# testsmd.net
KiCad netlist of a schematic drawn in EAGLE
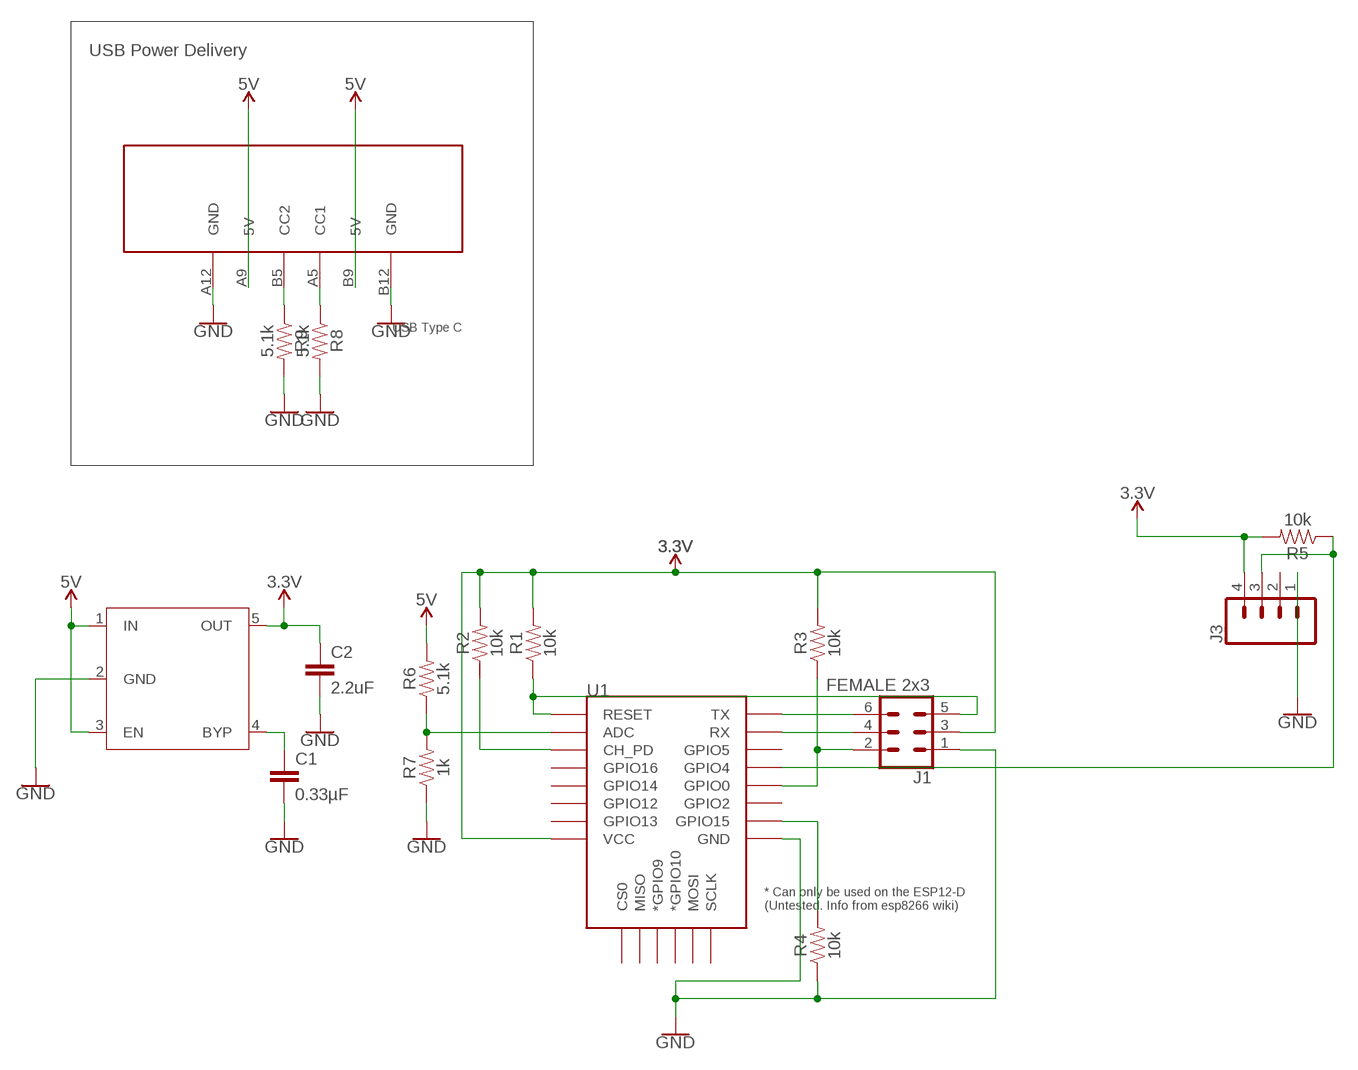
[diagram p0: schematic, sheet 1]

(export (version "E")
  (design (tool "Eeschema 10.0.6"))
  (components
    (comp (ref "C1")
      (value "0.33µF")
      (footprint "eagle-import:0805")
      (libsource (lib "eagle-import") (part "0.33UF/330NF-0805-50V-10%"))
    )
    (comp (ref "C2")
      (value "2.2uF")
      (footprint "eagle-import:1206")
      (libsource (lib "eagle-import") (part "2.2UF-1206-50V-10%"))
    )
    (comp (ref "J1")
      (value "FEMALE 2x3")
      (footprint "eagle-import:2X3")
      (libsource (lib "eagle-import") (part "CONN_03X2FEMALE"))
    )
    (comp (ref "J3")
      (value "CONN_04")
      (footprint "eagle-import:1X04")
      (libsource (lib "eagle-import") (part "CONN_04"))
    )
    (comp (ref "R1")
      (value "10k")
      (footprint "eagle-import:0805")
      (libsource (lib "eagle-import") (part "0.75OHM-0805-1/4W-1%"))
    )
    (comp (ref "R2")
      (value "10k")
      (footprint "eagle-import:0805")
      (libsource (lib "eagle-import") (part "0.75OHM-0805-1/4W-1%"))
    )
    (comp (ref "R3")
      (value "10k")
      (footprint "eagle-import:0805")
      (libsource (lib "eagle-import") (part "0.75OHM-0805-1/4W-1%"))
    )
    (comp (ref "R4")
      (value "10k")
      (footprint "eagle-import:0805")
      (libsource (lib "eagle-import") (part "0.75OHM-0805-1/4W-1%"))
    )
    (comp (ref "R5")
      (value "10k")
      (footprint "eagle-import:0805")
      (libsource (lib "eagle-import") (part "0.75OHM-0805-1/4W-1%"))
    )
    (comp (ref "R6")
      (value "5.1k")
      (footprint "eagle-import:0805")
      (libsource (lib "eagle-import") (part "0.75OHM-0805-1/4W-1%"))
    )
    (comp (ref "R7")
      (value "1k")
      (footprint "eagle-import:0805")
      (libsource (lib "eagle-import") (part "0.75OHM-0805-1/4W-1%"))
    )
    (comp (ref "R8")
      (value "5.1k")
      (footprint "eagle-import:0805")
      (libsource (lib "eagle-import") (part "0.75OHM-0805-1/4W-1%"))
    )
    (comp (ref "R9")
      (value "5.1k")
      (footprint "eagle-import:0805")
      (libsource (lib "eagle-import") (part "0.75OHM-0805-1/4W-1%"))
    )
    (comp (ref "U$1")
      (value "MIC5219")
      (footprint "eagle-import:SOT95P280X145-5N")
      (libsource (lib "eagle-import") (part "MIC5219"))
    )
    (comp (ref "U$3")
      (value "USBC6PIN")
      (footprint "eagle-import:USBC6PIN")
      (libsource (lib "eagle-import") (part "USBC6PIN"))
    )
    (comp (ref "U1")
      (value "ESP12ESMD")
      (footprint "eagle-import:ESP12E-SMD")
      (libsource (lib "eagle-import") (part "ESP12ESMD"))
    )
  )
  (nets
    (net (code "1") (name "3.3V") (class "Default")
      (node (ref "C2") (pin "1") (pinfunction "1_1") (pintype "passive"))
      (node (ref "J1") (pin "3") (pinfunction "3_3") (pintype "bidirectional"))
      (node (ref "J3") (pin "4") (pinfunction "4_4") (pintype "passive"))
      (node (ref "R1") (pin "2") (pinfunction "2_2") (pintype "passive"))
      (node (ref "R2") (pin "2") (pinfunction "2_2") (pintype "passive"))
      (node (ref "R3") (pin "2") (pinfunction "2_2") (pintype "passive"))
      (node (ref "R5") (pin "2") (pinfunction "2_2") (pintype "passive"))
      (node (ref "U$1") (pin "5") (pinfunction "OUT_5") (pintype "bidirectional"))
      (node (ref "U1") (pin "VCC") (pinfunction "VCC_VCC") (pintype "bidirectional"))
    )
    (net (code "2") (name "5V") (class "Default")
      (node (ref "R6") (pin "2") (pinfunction "2_2") (pintype "passive"))
      (node (ref "U$1") (pin "1") (pinfunction "IN_1") (pintype "bidirectional"))
      (node (ref "U$1") (pin "3") (pinfunction "EN_3") (pintype "bidirectional"))
      (node (ref "U$3") (pin "A9") (pinfunction "5V_A9") (pintype "bidirectional"))
      (node (ref "U$3") (pin "B9") (pinfunction "5V_B9") (pintype "bidirectional"))
    )
    (net (code "3") (name "GND") (class "Default")
      (node (ref "C1") (pin "2") (pinfunction "2_2") (pintype "passive"))
      (node (ref "C2") (pin "2") (pinfunction "2_2") (pintype "passive"))
      (node (ref "J1") (pin "1") (pinfunction "1_1") (pintype "bidirectional"))
      (node (ref "J3") (pin "1") (pinfunction "1_1") (pintype "passive"))
      (node (ref "R4") (pin "1") (pinfunction "1_1") (pintype "passive"))
      (node (ref "R7") (pin "1") (pinfunction "1_1") (pintype "passive"))
      (node (ref "R8") (pin "2") (pinfunction "2_2") (pintype "passive"))
      (node (ref "R9") (pin "2") (pinfunction "2_2") (pintype "passive"))
      (node (ref "U$1") (pin "2") (pinfunction "GND_2") (pintype "bidirectional"))
      (node (ref "U$3") (pin "A12") (pinfunction "GND_A12") (pintype "bidirectional"))
      (node (ref "U$3") (pin "B12") (pinfunction "GND_B12") (pintype "bidirectional"))
      (node (ref "U1") (pin "GND") (pinfunction "GND_GND") (pintype "bidirectional"))
    )
    (net (code "4") (name "Net-(J1-Pad2)") (class "Default")
      (node (ref "J1") (pin "2") (pinfunction "2_2") (pintype "bidirectional"))
      (node (ref "R3") (pin "1") (pinfunction "1_1") (pintype "passive"))
      (node (ref "U1") (pin "GPIO0") (pinfunction "GPIO0_GPIO0") (pintype "bidirectional"))
    )
    (net (code "5") (name "Net-(J1-Pad5)") (class "Default")
      (node (ref "J1") (pin "5") (pinfunction "5_5") (pintype "bidirectional"))
      (node (ref "R1") (pin "1") (pinfunction "1_1") (pintype "passive"))
      (node (ref "U1") (pin "RESET") (pinfunction "RESET_RESET") (pintype "bidirectional"))
    )
    (net (code "6") (name "Net-(J3-Pad3)") (class "Default")
      (node (ref "J3") (pin "3") (pinfunction "3_3") (pintype "passive"))
      (node (ref "R5") (pin "1") (pinfunction "1_1") (pintype "passive"))
      (node (ref "U1") (pin "GPIO4") (pinfunction "GPIO4_GPIO4") (pintype "bidirectional"))
    )
    (net (code "7") (name "Net-(R2-Pad1)") (class "Default")
      (node (ref "R2") (pin "1") (pinfunction "1_1") (pintype "passive"))
      (node (ref "U1") (pin "CH_PD") (pinfunction "CH_PD_CH_PD") (pintype "bidirectional"))
    )
    (net (code "8") (name "Net-(R4-Pad2)") (class "Default")
      (node (ref "R4") (pin "2") (pinfunction "2_2") (pintype "passive"))
      (node (ref "U1") (pin "GPIO15") (pinfunction "GPIO15_GPIO15") (pintype "bidirectional"))
    )
    (net (code "9") (name "Net-(R6-Pad1)") (class "Default")
      (node (ref "R6") (pin "1") (pinfunction "1_1") (pintype "passive"))
      (node (ref "R7") (pin "2") (pinfunction "2_2") (pintype "passive"))
      (node (ref "U1") (pin "ADC") (pinfunction "ADC_ADC") (pintype "bidirectional"))
    )
    (net (code "10") (name "Net-(U$1-BYP)") (class "Default")
      (node (ref "C1") (pin "1") (pinfunction "1_1") (pintype "passive"))
      (node (ref "U$1") (pin "4") (pinfunction "BYP_4") (pintype "bidirectional"))
    )
    (net (code "11") (name "Net-(U$3-CC1)") (class "Default")
      (node (ref "R8") (pin "1") (pinfunction "1_1") (pintype "passive"))
      (node (ref "U$3") (pin "A5") (pinfunction "CC1_A5") (pintype "bidirectional"))
    )
    (net (code "12") (name "Net-(U$3-CC2)") (class "Default")
      (node (ref "R9") (pin "1") (pinfunction "1_1") (pintype "passive"))
      (node (ref "U$3") (pin "B5") (pinfunction "CC2_B5") (pintype "bidirectional"))
    )
    (net (code "13") (name "Net-(U1-RX)") (class "Default")
      (node (ref "J1") (pin "4") (pinfunction "4_4") (pintype "bidirectional"))
      (node (ref "U1") (pin "RXD0") (pinfunction "RX_RXD0") (pintype "bidirectional"))
    )
    (net (code "14") (name "Net-(U1-TX)") (class "Default")
      (node (ref "J1") (pin "6") (pinfunction "6_6") (pintype "bidirectional"))
      (node (ref "U1") (pin "TXD0") (pinfunction "TX_TXD0") (pintype "bidirectional"))
    )
    (net (code "15") (name "unconnected-(J3-Pad2)") (class "Default")
      (node (ref "J3") (pin "2") (pinfunction "2_2") (pintype "passive"))
    )
    (net (code "16") (name "unconnected-(U1-*GPIO9-PadGPIO9)") (class "Default")
      (node (ref "U1") (pin "GPIO9") (pinfunction "*GPIO9_GPIO9") (pintype "bidirectional"))
    )
    (net (code "17") (name "unconnected-(U1-*GPIO10-PadGPIO10)") (class "Default")
      (node (ref "U1") (pin "GPIO10") (pinfunction "*GPIO10_GPIO10") (pintype "bidirectional"))
    )
    (net (code "18") (name "unconnected-(U1-PadCS0)") (class "Default")
      (node (ref "U1") (pin "CS0") (pinfunction "CS0_CS0") (pintype "bidirectional"))
    )
    (net (code "19") (name "unconnected-(U1-PadGPIO2)") (class "Default")
      (node (ref "U1") (pin "GPIO2") (pinfunction "GPIO2_GPIO2") (pintype "bidirectional"))
    )
    (net (code "20") (name "unconnected-(U1-PadGPIO5)") (class "Default")
      (node (ref "U1") (pin "GPIO5") (pinfunction "GPIO5_GPIO5") (pintype "bidirectional"))
    )
    (net (code "21") (name "unconnected-(U1-PadGPIO12)") (class "Default")
      (node (ref "U1") (pin "GPIO12") (pinfunction "GPIO12_GPIO12") (pintype "bidirectional"))
    )
    (net (code "22") (name "unconnected-(U1-PadGPIO13)") (class "Default")
      (node (ref "U1") (pin "GPIO13") (pinfunction "GPIO13_GPIO13") (pintype "bidirectional"))
    )
    (net (code "23") (name "unconnected-(U1-PadGPIO14)") (class "Default")
      (node (ref "U1") (pin "GPIO14") (pinfunction "GPIO14_GPIO14") (pintype "bidirectional"))
    )
    (net (code "24") (name "unconnected-(U1-PadGPIO16)") (class "Default")
      (node (ref "U1") (pin "GPIO16") (pinfunction "GPIO16_GPIO16") (pintype "bidirectional"))
    )
    (net (code "25") (name "unconnected-(U1-PadMISO)") (class "Default")
      (node (ref "U1") (pin "MISO") (pinfunction "MISO_MISO") (pintype "bidirectional"))
    )
    (net (code "26") (name "unconnected-(U1-PadMOSI)") (class "Default")
      (node (ref "U1") (pin "MOSI") (pinfunction "MOSI_MOSI") (pintype "bidirectional"))
    )
    (net (code "27") (name "unconnected-(U1-PadSCLK)") (class "Default")
      (node (ref "U1") (pin "SCLK") (pinfunction "SCLK_SCLK") (pintype "bidirectional"))
    )
  )
)
